# Sheet2.net
KiCad netlist of a schematic drawn in Altium Designer
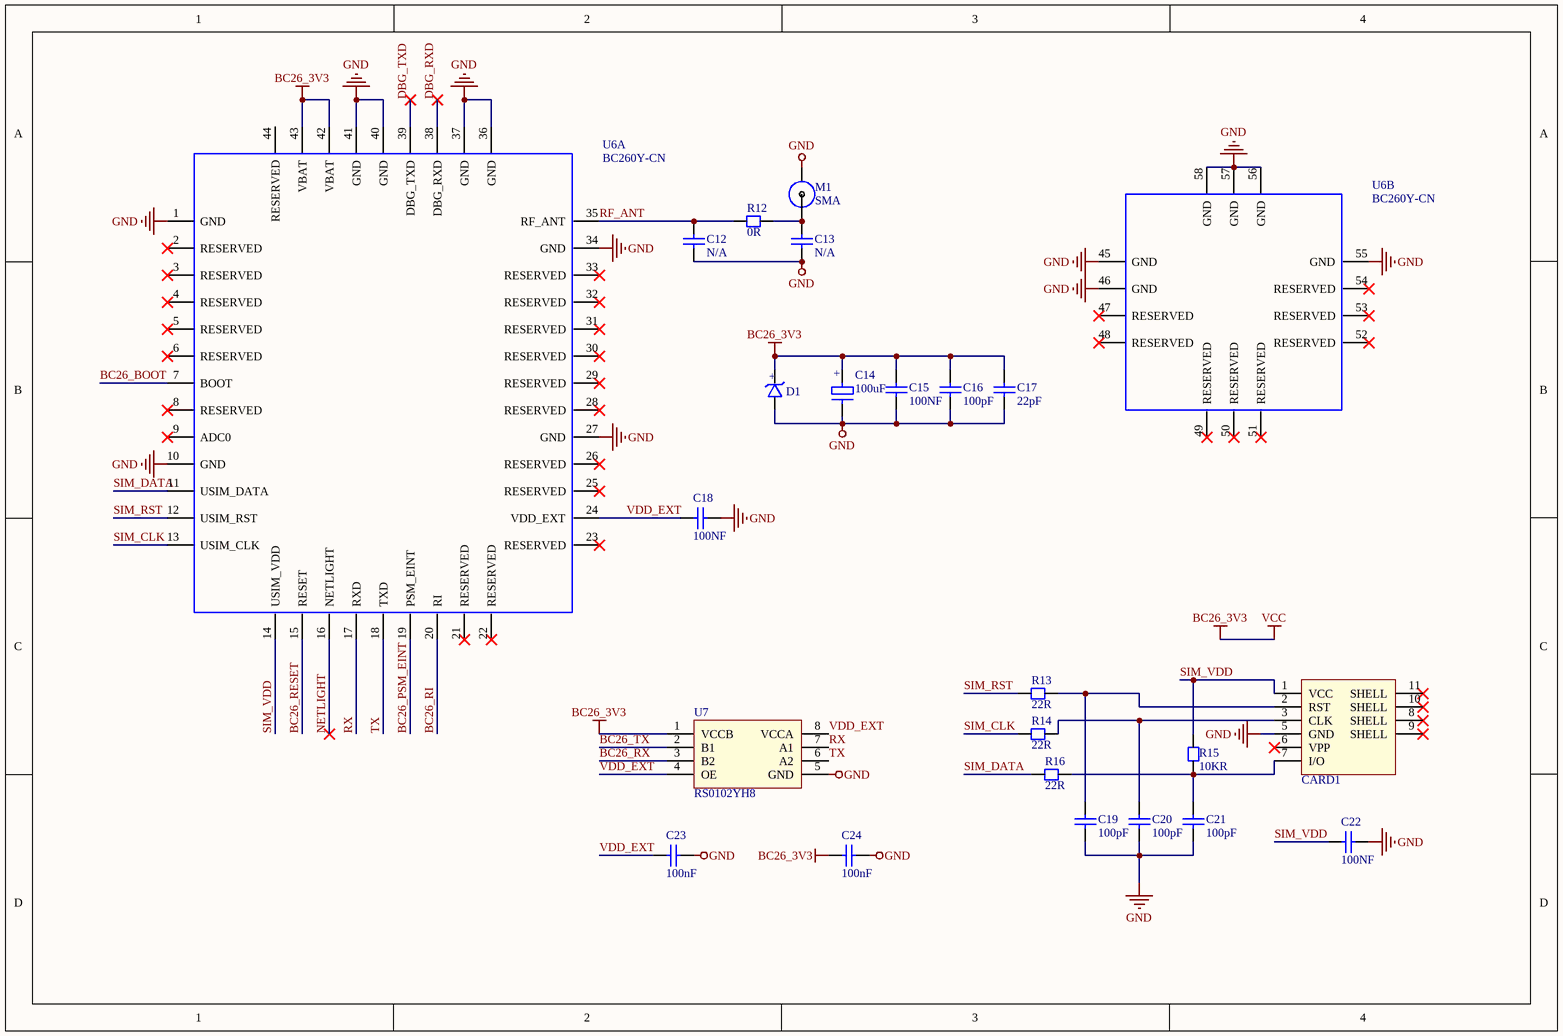
[diagram p0: Sheet2.SchDoc]

(export (version "E")
  (design (tool "Eeschema 10.0.6"))
  (components
    (comp (ref "C12")
      (value "N/A")
      (footprint "CC1608-0603")
      (description "贴片电容")
      (libsource (lib "tianxiaohua_Schlib") (part "Chip capacitor"))
    )
    (comp (ref "C13")
      (value "N/A")
      (footprint "CC1608-0603")
      (description "贴片电容")
      (libsource (lib "tianxiaohua_Schlib") (part "Chip capacitor"))
    )
    (comp (ref "C14")
      (value "100uF")
      (footprint "CASE-B_3528")
      (description "钽电容 3528封装")
      (libsource (lib "tianxiaohua_Schlib") (part "Chip capacitor TAJB107K006RNJ"))
    )
    (comp (ref "C15")
      (value "100NF")
      (footprint "CC1608-0603")
      (description "贴片电容")
      (libsource (lib "tianxiaohua_Schlib") (part "Chip capacitor"))
    )
    (comp (ref "C16")
      (value "100pF")
      (footprint "CC1608-0603")
      (description "贴片电容")
      (libsource (lib "tianxiaohua_Schlib") (part "Chip capacitor"))
    )
    (comp (ref "C17")
      (value "22pF")
      (footprint "CC1608-0603")
      (description "贴片电容")
      (libsource (lib "tianxiaohua_Schlib") (part "Chip capacitor"))
    )
    (comp (ref "C18")
      (value "100NF")
      (footprint "CC1608-0603")
      (description "贴片电容")
      (libsource (lib "tianxiaohua_Schlib") (part "Chip capacitor"))
    )
    (comp (ref "C19")
      (value "100pF")
      (footprint "CC1608-0603")
      (description "贴片电容")
      (libsource (lib "tianxiaohua_Schlib") (part "Chip capacitor"))
    )
    (comp (ref "C20")
      (value "100pF")
      (footprint "CC1608-0603")
      (description "贴片电容")
      (libsource (lib "tianxiaohua_Schlib") (part "Chip capacitor"))
    )
    (comp (ref "C21")
      (value "100pF")
      (footprint "CC1608-0603")
      (description "贴片电容")
      (libsource (lib "tianxiaohua_Schlib") (part "Chip capacitor"))
    )
    (comp (ref "C22")
      (value "100NF")
      (footprint "CC1608-0603")
      (description "贴片电容")
      (libsource (lib "tianxiaohua_Schlib") (part "Chip capacitor"))
    )
    (comp (ref "C23")
      (value "100nF")
      (footprint "CC1608-0603")
      (description "贴片电容")
      (libsource (lib "tianxiaohua_Schlib") (part "Chip capacitor"))
    )
    (comp (ref "C24")
      (value "100nF")
      (footprint "CC1608-0603")
      (description "贴片电容")
      (libsource (lib "tianxiaohua_Schlib") (part "Chip capacitor"))
    )
    (comp (ref "CARD1")
      (value "SIM-6P")
      (footprint "SIM-P6")
      (description "sim卡座，自弹出样式，可以插入小卡")
      (libsource (lib "tianxiaohua_Schlib") (part "SIM-6P"))
    )
    (comp (ref "D1")
      (value "SMBJ3.3A")
      (footprint "DO214AA(SMB)")
      (description "3.3V稳压管，缓解瞬间电压冲击")
      (libsource (lib "tianxiaohua_Schlib") (part "SMBJ3.3A"))
    )
    (comp (ref "M1")
      (value "SMA")
      (footprint "SMA-KWE")
      (description "天线")
      (libsource (lib "tianxiaohua_Schlib") (part "SMA"))
    )
    (comp (ref "R12")
      (value "0R")
      (footprint "CR1608-0603")
      (description "贴片电阻")
      (libsource (lib "tianxiaohua_Schlib") (part "Chip resistor"))
    )
    (comp (ref "R13")
      (value "22R")
      (footprint "CR1608-0603")
      (description "贴片电阻")
      (libsource (lib "") (part "Chip resistor_1"))
    )
    (comp (ref "R14")
      (value "22R")
      (footprint "CR1608-0603")
      (description "贴片电阻")
      (libsource (lib "") (part "Chip resistor_1"))
    )
    (comp (ref "R15")
      (value "10KR")
      (footprint "CR1608-0603")
      (description "贴片电阻")
      (libsource (lib "") (part "Chip resistor_2"))
    )
    (comp (ref "R16")
      (value "22R")
      (footprint "CR1608-0603")
      (description "贴片电阻")
      (libsource (lib "") (part "Chip resistor_1"))
    )
    (comp (ref "U6")
      (value "BC260Y-CN")
      (footprint "BC260Y-CN")
      (fields (field (name "MANUFACTURER") "QUECTEL"))
      (libsource (lib "tianxiaohua_Schlib") (part "BC260Y-CN"))
    )
    (comp (ref "U7")
      (value "RS0102YH8")
      (footprint "SOT-23-8")
      (description "电平转换芯片")
      (libsource (lib "tianxiaohua_Schlib") (part "RS0102"))
    )
  )
  (nets
    (net (code "1") (name "/BC26_BOOT") (class "Default")
      (node (ref "U6") (pin "7") (pinfunction "BOOT_7") (pintype "passive"))
    )
    (net (code "2") (name "/BC26_PSM_EINT") (class "Default")
      (node (ref "U6") (pin "19") (pinfunction "PSM_EINT_19") (pintype "passive"))
    )
    (net (code "3") (name "/BC26_RESET") (class "Default")
      (node (ref "U6") (pin "15") (pinfunction "RESET_15") (pintype "passive"))
    )
    (net (code "4") (name "/BC26_RI") (class "Default")
      (node (ref "U6") (pin "20") (pinfunction "RI_20") (pintype "passive"))
    )
    (net (code "5") (name "/BC26_RX") (class "Default")
      (node (ref "U7") (pin "3") (pinfunction "B2_3") (pintype "passive"))
    )
    (net (code "6") (name "/BC26_TX") (class "Default")
      (node (ref "U7") (pin "2") (pinfunction "B1_2") (pintype "passive"))
    )
    (net (code "7") (name "/DBG_RXD") (class "Default")
      (node (ref "U6") (pin "38") (pinfunction "DBG_RXD_38") (pintype "passive+no_connect"))
    )
    (net (code "8") (name "/DBG_TXD") (class "Default")
      (node (ref "U6") (pin "39") (pinfunction "DBG_TXD_39") (pintype "passive+no_connect"))
    )
    (net (code "9") (name "/NETLIGHT") (class "Default")
      (node (ref "U6") (pin "16") (pinfunction "NETLIGHT_16") (pintype "passive+no_connect"))
    )
    (net (code "10") (name "/RF_ANT") (class "Default")
      (node (ref "C12") (pin "1") (pinfunction "1_1") (pintype "passive"))
      (node (ref "R12") (pin "2") (pinfunction "2_2") (pintype "passive"))
      (node (ref "U6") (pin "35") (pinfunction "RF_ANT_35") (pintype "passive"))
    )
    (net (code "11") (name "/RX") (class "Default")
      (node (ref "U6") (pin "17") (pinfunction "RXD_17") (pintype "passive"))
      (node (ref "U7") (pin "7") (pinfunction "A1_7") (pintype "passive"))
    )
    (net (code "12") (name "/SIM_CLK") (class "Default")
      (node (ref "R14") (pin "1") (pinfunction "1_1") (pintype "passive"))
      (node (ref "U6") (pin "13") (pinfunction "USIM_CLK_13") (pintype "passive"))
    )
    (net (code "13") (name "/SIM_DATA") (class "Default")
      (node (ref "R16") (pin "1") (pinfunction "1_1") (pintype "passive"))
      (node (ref "U6") (pin "11") (pinfunction "USIM_DATA_11") (pintype "passive"))
    )
    (net (code "14") (name "/SIM_RST") (class "Default")
      (node (ref "R13") (pin "1") (pinfunction "1_1") (pintype "passive"))
      (node (ref "U6") (pin "12") (pinfunction "USIM_RST_12") (pintype "passive"))
    )
    (net (code "15") (name "/SIM_VDD") (class "Default")
      (node (ref "C22") (pin "2") (pinfunction "2_2") (pintype "passive"))
      (node (ref "CARD1") (pin "1") (pinfunction "VCC_1") (pintype "passive"))
      (node (ref "R15") (pin "1") (pinfunction "1_1") (pintype "passive"))
      (node (ref "U6") (pin "14") (pinfunction "USIM_VDD_14") (pintype "passive"))
    )
    (net (code "16") (name "/TX") (class "Default")
      (node (ref "U6") (pin "18") (pinfunction "TXD_18") (pintype "passive"))
      (node (ref "U7") (pin "6") (pinfunction "A2_6") (pintype "passive"))
    )
    (net (code "17") (name "/VDD_EXT") (class "Default")
      (node (ref "C18") (pin "2") (pinfunction "2_2") (pintype "passive"))
      (node (ref "C23") (pin "1") (pinfunction "1_1") (pintype "passive"))
      (node (ref "U6") (pin "24") (pinfunction "VDD_EXT_24") (pintype "passive"))
      (node (ref "U7") (pin "4") (pinfunction "OE_4") (pintype "passive"))
      (node (ref "U7") (pin "8") (pinfunction "VCCA_8") (pintype "passive"))
    )
    (net (code "18") (name "BC26_3V3") (class "Default")
      (node (ref "C14") (pin "1") (pinfunction "+_1") (pintype "passive"))
      (node (ref "C15") (pin "2") (pinfunction "2_2") (pintype "passive"))
      (node (ref "C16") (pin "2") (pinfunction "2_2") (pintype "passive"))
      (node (ref "C17") (pin "2") (pinfunction "2_2") (pintype "passive"))
      (node (ref "C24") (pin "1") (pinfunction "1_1") (pintype "passive"))
      (node (ref "D1") (pin "1") (pinfunction "1_1") (pintype "passive"))
      (node (ref "U6") (pin "42") (pinfunction "VBAT_42") (pintype "passive"))
      (node (ref "U6") (pin "43") (pinfunction "VBAT_43") (pintype "passive"))
      (node (ref "U7") (pin "1") (pinfunction "VCCB_1") (pintype "passive"))
    )
    (net (code "19") (name "GND") (class "Default")
      (node (ref "C12") (pin "2") (pinfunction "2_2") (pintype "passive"))
      (node (ref "C13") (pin "1") (pinfunction "1_1") (pintype "passive"))
      (node (ref "C14") (pin "2") (pinfunction "-_2") (pintype "passive"))
      (node (ref "C15") (pin "1") (pinfunction "1_1") (pintype "passive"))
      (node (ref "C16") (pin "1") (pinfunction "1_1") (pintype "passive"))
      (node (ref "C17") (pin "1") (pinfunction "1_1") (pintype "passive"))
      (node (ref "C18") (pin "1") (pinfunction "1_1") (pintype "passive"))
      (node (ref "C19") (pin "1") (pinfunction "1_1") (pintype "passive"))
      (node (ref "C20") (pin "1") (pinfunction "1_1") (pintype "passive"))
      (node (ref "C21") (pin "1") (pinfunction "1_1") (pintype "passive"))
      (node (ref "C22") (pin "1") (pinfunction "1_1") (pintype "passive"))
      (node (ref "C23") (pin "2") (pinfunction "2_2") (pintype "passive"))
      (node (ref "C24") (pin "2") (pinfunction "2_2") (pintype "passive"))
      (node (ref "CARD1") (pin "5") (pinfunction "GND_5") (pintype "passive"))
      (node (ref "D1") (pin "2") (pinfunction "2_2") (pintype "passive"))
      (node (ref "M1") (pin "2") (pinfunction "GND_2") (pintype "passive"))
      (node (ref "U6") (pin "1") (pinfunction "GND_1") (pintype "passive"))
      (node (ref "U6") (pin "10") (pinfunction "GND_10") (pintype "passive"))
      (node (ref "U6") (pin "27") (pinfunction "GND_27") (pintype "passive"))
      (node (ref "U6") (pin "34") (pinfunction "GND_34") (pintype "passive"))
      (node (ref "U6") (pin "36") (pinfunction "GND_36") (pintype "passive"))
      (node (ref "U6") (pin "37") (pinfunction "GND_37") (pintype "passive"))
      (node (ref "U6") (pin "40") (pinfunction "GND_40") (pintype "passive"))
      (node (ref "U6") (pin "41") (pinfunction "GND_41") (pintype "passive"))
      (node (ref "U6") (pin "45") (pinfunction "GND_45") (pintype "passive"))
      (node (ref "U6") (pin "46") (pinfunction "GND_46") (pintype "passive"))
      (node (ref "U6") (pin "55") (pinfunction "GND_55") (pintype "passive"))
      (node (ref "U6") (pin "56") (pinfunction "GND_56") (pintype "passive"))
      (node (ref "U6") (pin "57") (pinfunction "GND_57") (pintype "passive"))
      (node (ref "U6") (pin "58") (pinfunction "GND_58") (pintype "passive"))
      (node (ref "U7") (pin "5") (pinfunction "GND_5") (pintype "passive"))
    )
    (net (code "20") (name "Net-(CARD1-CLK)") (class "Default")
      (node (ref "C20") (pin "2") (pinfunction "2_2") (pintype "passive"))
      (node (ref "CARD1") (pin "3") (pinfunction "CLK_3") (pintype "passive"))
      (node (ref "R14") (pin "2") (pinfunction "2_2") (pintype "passive"))
    )
    (net (code "21") (name "Net-(CARD1-I{slash}O)") (class "Default")
      (node (ref "C21") (pin "2") (pinfunction "2_2") (pintype "passive"))
      (node (ref "CARD1") (pin "7") (pinfunction "I/O_7") (pintype "passive"))
      (node (ref "R15") (pin "2") (pinfunction "2_2") (pintype "passive"))
      (node (ref "R16") (pin "2") (pinfunction "2_2") (pintype "passive"))
    )
    (net (code "22") (name "Net-(CARD1-RST)") (class "Default")
      (node (ref "C19") (pin "2") (pinfunction "2_2") (pintype "passive"))
      (node (ref "CARD1") (pin "2") (pinfunction "RST_2") (pintype "passive"))
      (node (ref "R13") (pin "2") (pinfunction "2_2") (pintype "passive"))
    )
    (net (code "23") (name "Net-(M1-M)") (class "Default")
      (node (ref "C13") (pin "2") (pinfunction "2_2") (pintype "passive"))
      (node (ref "M1") (pin "1") (pinfunction "M_1") (pintype "passive"))
      (node (ref "R12") (pin "1") (pinfunction "1_1") (pintype "passive"))
    )
    (net (code "24") (name "unconnected-(CARD1-SHELL-Pad8)") (class "Default")
      (node (ref "CARD1") (pin "8") (pinfunction "SHELL_8") (pintype "passive+no_connect"))
    )
    (net (code "25") (name "unconnected-(CARD1-SHELL-Pad9)") (class "Default")
      (node (ref "CARD1") (pin "9") (pinfunction "SHELL_9") (pintype "passive+no_connect"))
    )
    (net (code "26") (name "unconnected-(CARD1-SHELL-Pad10)") (class "Default")
      (node (ref "CARD1") (pin "10") (pinfunction "SHELL_10") (pintype "passive+no_connect"))
    )
    (net (code "27") (name "unconnected-(CARD1-SHELL-Pad11)") (class "Default")
      (node (ref "CARD1") (pin "11") (pinfunction "SHELL_11") (pintype "passive+no_connect"))
    )
    (net (code "28") (name "unconnected-(CARD1-VPP-Pad6)") (class "Default")
      (node (ref "CARD1") (pin "6") (pinfunction "VPP_6") (pintype "passive+no_connect"))
    )
    (net (code "29") (name "unconnected-(U6A-ADC0-Pad9)") (class "Default")
      (node (ref "U6") (pin "9") (pinfunction "ADC0_9") (pintype "passive+no_connect"))
    )
    (net (code "30") (name "unconnected-(U6A-RESERVED-Pad2)") (class "Default")
      (node (ref "U6") (pin "2") (pinfunction "RESERVED_2") (pintype "passive+no_connect"))
    )
    (net (code "31") (name "unconnected-(U6A-RESERVED-Pad3)") (class "Default")
      (node (ref "U6") (pin "3") (pinfunction "RESERVED_3") (pintype "passive+no_connect"))
    )
    (net (code "32") (name "unconnected-(U6A-RESERVED-Pad4)") (class "Default")
      (node (ref "U6") (pin "4") (pinfunction "RESERVED_4") (pintype "passive+no_connect"))
    )
    (net (code "33") (name "unconnected-(U6A-RESERVED-Pad5)") (class "Default")
      (node (ref "U6") (pin "5") (pinfunction "RESERVED_5") (pintype "passive+no_connect"))
    )
    (net (code "34") (name "unconnected-(U6A-RESERVED-Pad6)") (class "Default")
      (node (ref "U6") (pin "6") (pinfunction "RESERVED_6") (pintype "passive+no_connect"))
    )
    (net (code "35") (name "unconnected-(U6A-RESERVED-Pad8)") (class "Default")
      (node (ref "U6") (pin "8") (pinfunction "RESERVED_8") (pintype "passive+no_connect"))
    )
    (net (code "36") (name "unconnected-(U6A-RESERVED-Pad21)") (class "Default")
      (node (ref "U6") (pin "21") (pinfunction "RESERVED_21") (pintype "passive+no_connect"))
    )
    (net (code "37") (name "unconnected-(U6A-RESERVED-Pad22)") (class "Default")
      (node (ref "U6") (pin "22") (pinfunction "RESERVED_22") (pintype "passive+no_connect"))
    )
    (net (code "38") (name "unconnected-(U6A-RESERVED-Pad23)") (class "Default")
      (node (ref "U6") (pin "23") (pinfunction "RESERVED_23") (pintype "passive+no_connect"))
    )
    (net (code "39") (name "unconnected-(U6A-RESERVED-Pad25)") (class "Default")
      (node (ref "U6") (pin "25") (pinfunction "RESERVED_25") (pintype "passive+no_connect"))
    )
    (net (code "40") (name "unconnected-(U6A-RESERVED-Pad26)") (class "Default")
      (node (ref "U6") (pin "26") (pinfunction "RESERVED_26") (pintype "passive+no_connect"))
    )
    (net (code "41") (name "unconnected-(U6A-RESERVED-Pad28)") (class "Default")
      (node (ref "U6") (pin "28") (pinfunction "RESERVED_28") (pintype "passive+no_connect"))
    )
    (net (code "42") (name "unconnected-(U6A-RESERVED-Pad29)") (class "Default")
      (node (ref "U6") (pin "29") (pinfunction "RESERVED_29") (pintype "passive+no_connect"))
    )
    (net (code "43") (name "unconnected-(U6A-RESERVED-Pad30)") (class "Default")
      (node (ref "U6") (pin "30") (pinfunction "RESERVED_30") (pintype "passive+no_connect"))
    )
    (net (code "44") (name "unconnected-(U6A-RESERVED-Pad31)") (class "Default")
      (node (ref "U6") (pin "31") (pinfunction "RESERVED_31") (pintype "passive+no_connect"))
    )
    (net (code "45") (name "unconnected-(U6A-RESERVED-Pad32)") (class "Default")
      (node (ref "U6") (pin "32") (pinfunction "RESERVED_32") (pintype "passive+no_connect"))
    )
    (net (code "46") (name "unconnected-(U6A-RESERVED-Pad33)") (class "Default")
      (node (ref "U6") (pin "33") (pinfunction "RESERVED_33") (pintype "passive+no_connect"))
    )
    (net (code "47") (name "unconnected-(U6A-RESERVED-Pad44)") (class "Default")
      (node (ref "U6") (pin "44") (pinfunction "RESERVED_44") (pintype "passive"))
    )
    (net (code "48") (name "unconnected-(U6B-RESERVED-Pad47)") (class "Default")
      (node (ref "U6") (pin "47") (pinfunction "RESERVED_47") (pintype "passive+no_connect"))
    )
    (net (code "49") (name "unconnected-(U6B-RESERVED-Pad48)") (class "Default")
      (node (ref "U6") (pin "48") (pinfunction "RESERVED_48") (pintype "passive+no_connect"))
    )
    (net (code "50") (name "unconnected-(U6B-RESERVED-Pad49)") (class "Default")
      (node (ref "U6") (pin "49") (pinfunction "RESERVED_49") (pintype "passive+no_connect"))
    )
    (net (code "51") (name "unconnected-(U6B-RESERVED-Pad50)") (class "Default")
      (node (ref "U6") (pin "50") (pinfunction "RESERVED_50") (pintype "passive+no_connect"))
    )
    (net (code "52") (name "unconnected-(U6B-RESERVED-Pad51)") (class "Default")
      (node (ref "U6") (pin "51") (pinfunction "RESERVED_51") (pintype "passive+no_connect"))
    )
    (net (code "53") (name "unconnected-(U6B-RESERVED-Pad52)") (class "Default")
      (node (ref "U6") (pin "52") (pinfunction "RESERVED_52") (pintype "passive+no_connect"))
    )
    (net (code "54") (name "unconnected-(U6B-RESERVED-Pad53)") (class "Default")
      (node (ref "U6") (pin "53") (pinfunction "RESERVED_53") (pintype "passive+no_connect"))
    )
    (net (code "55") (name "unconnected-(U6B-RESERVED-Pad54)") (class "Default")
      (node (ref "U6") (pin "54") (pinfunction "RESERVED_54") (pintype "passive+no_connect"))
    )
  )
)
